# PlacaAquisicao.net
KiCad netlist of a schematic drawn in EAGLE
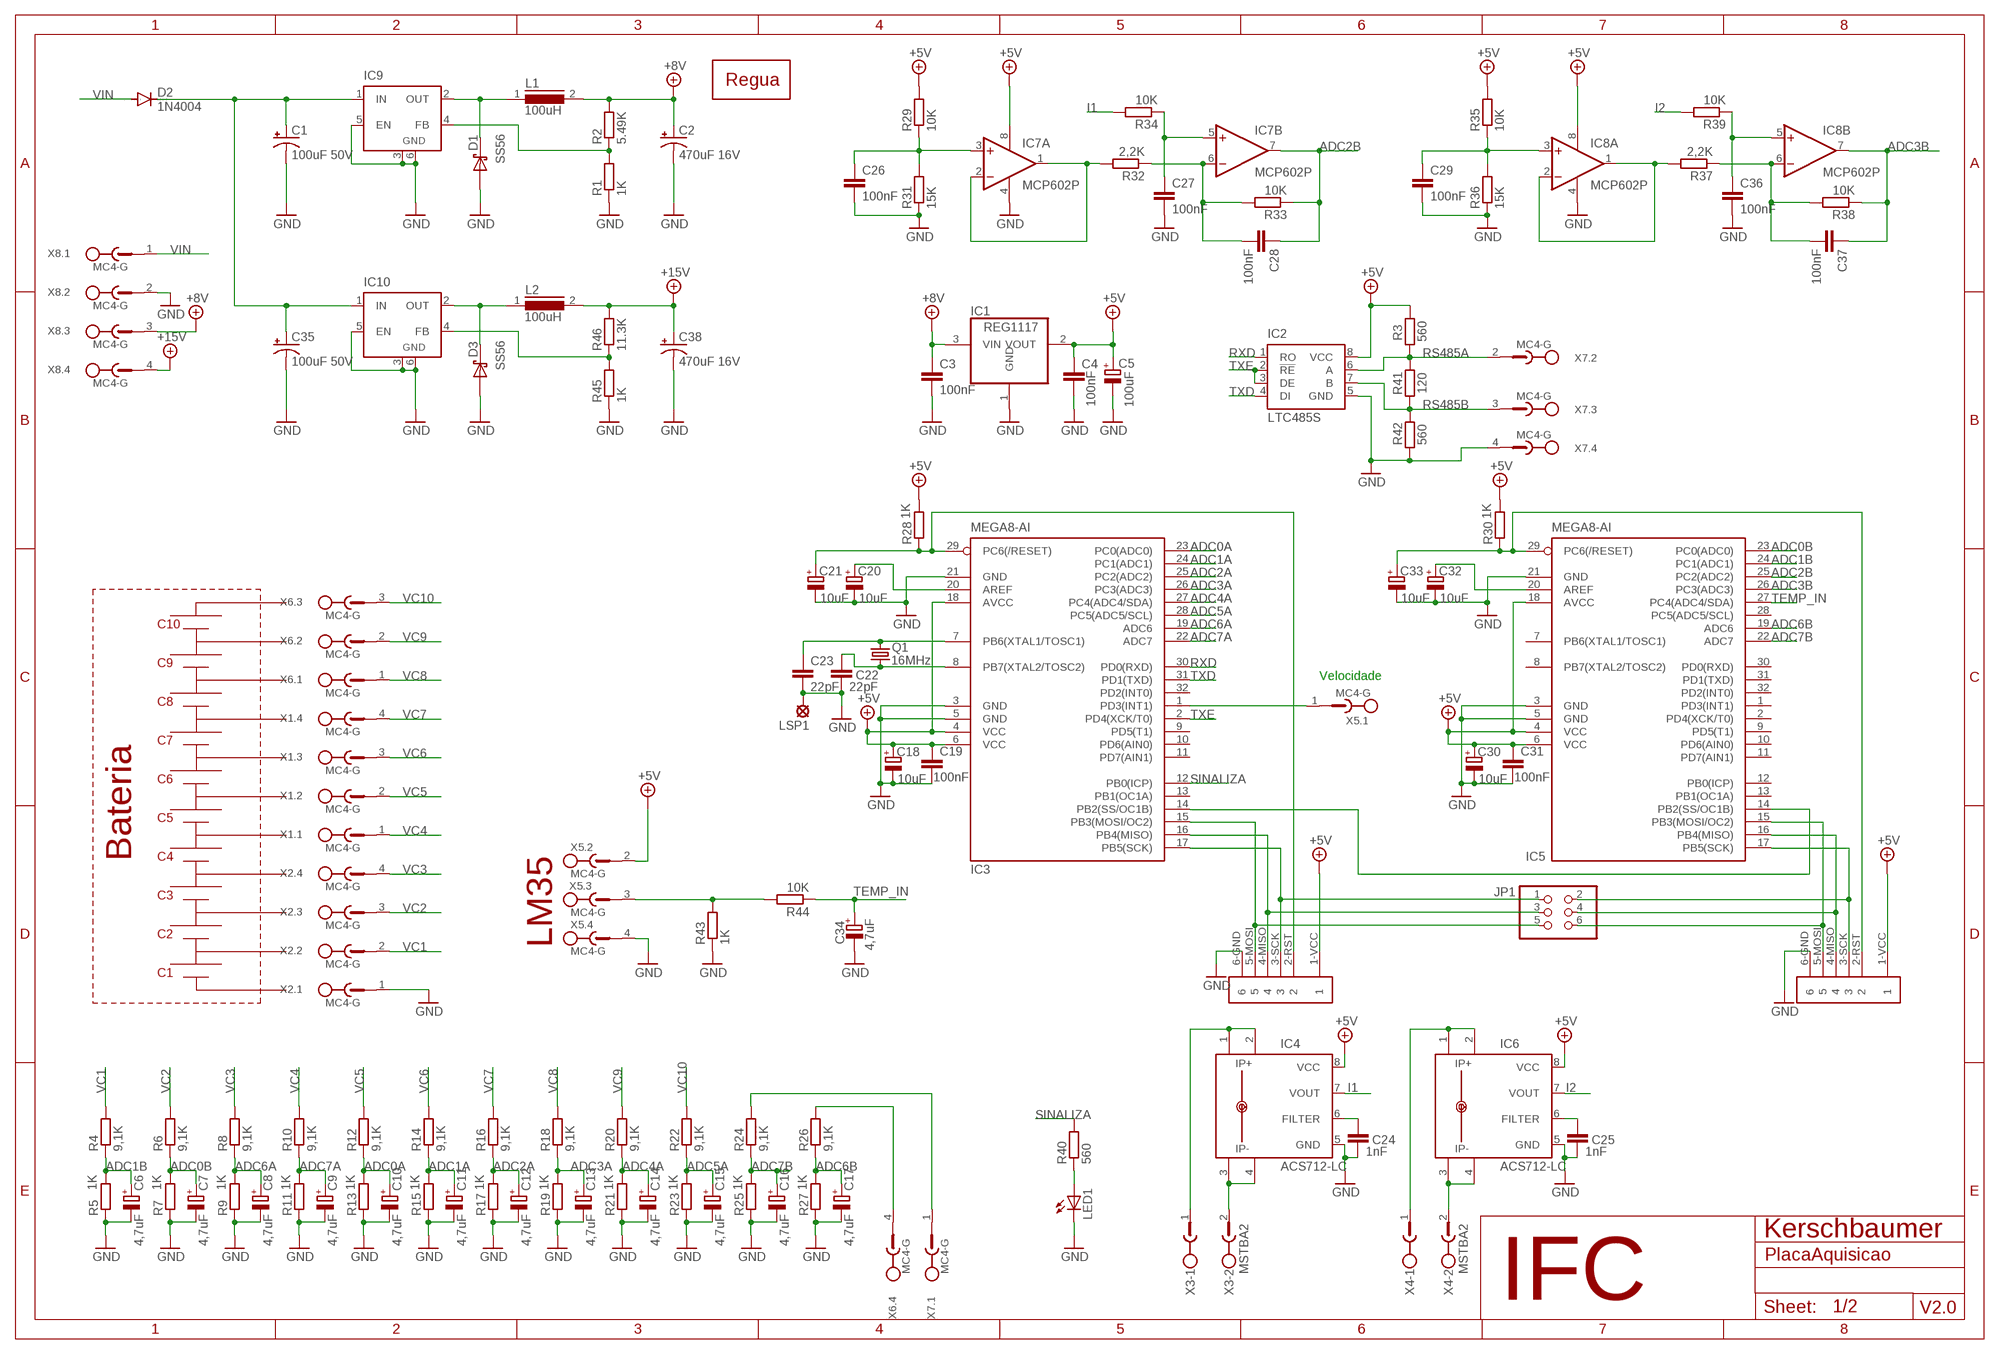
[diagram p0: schematic, sheet 1]
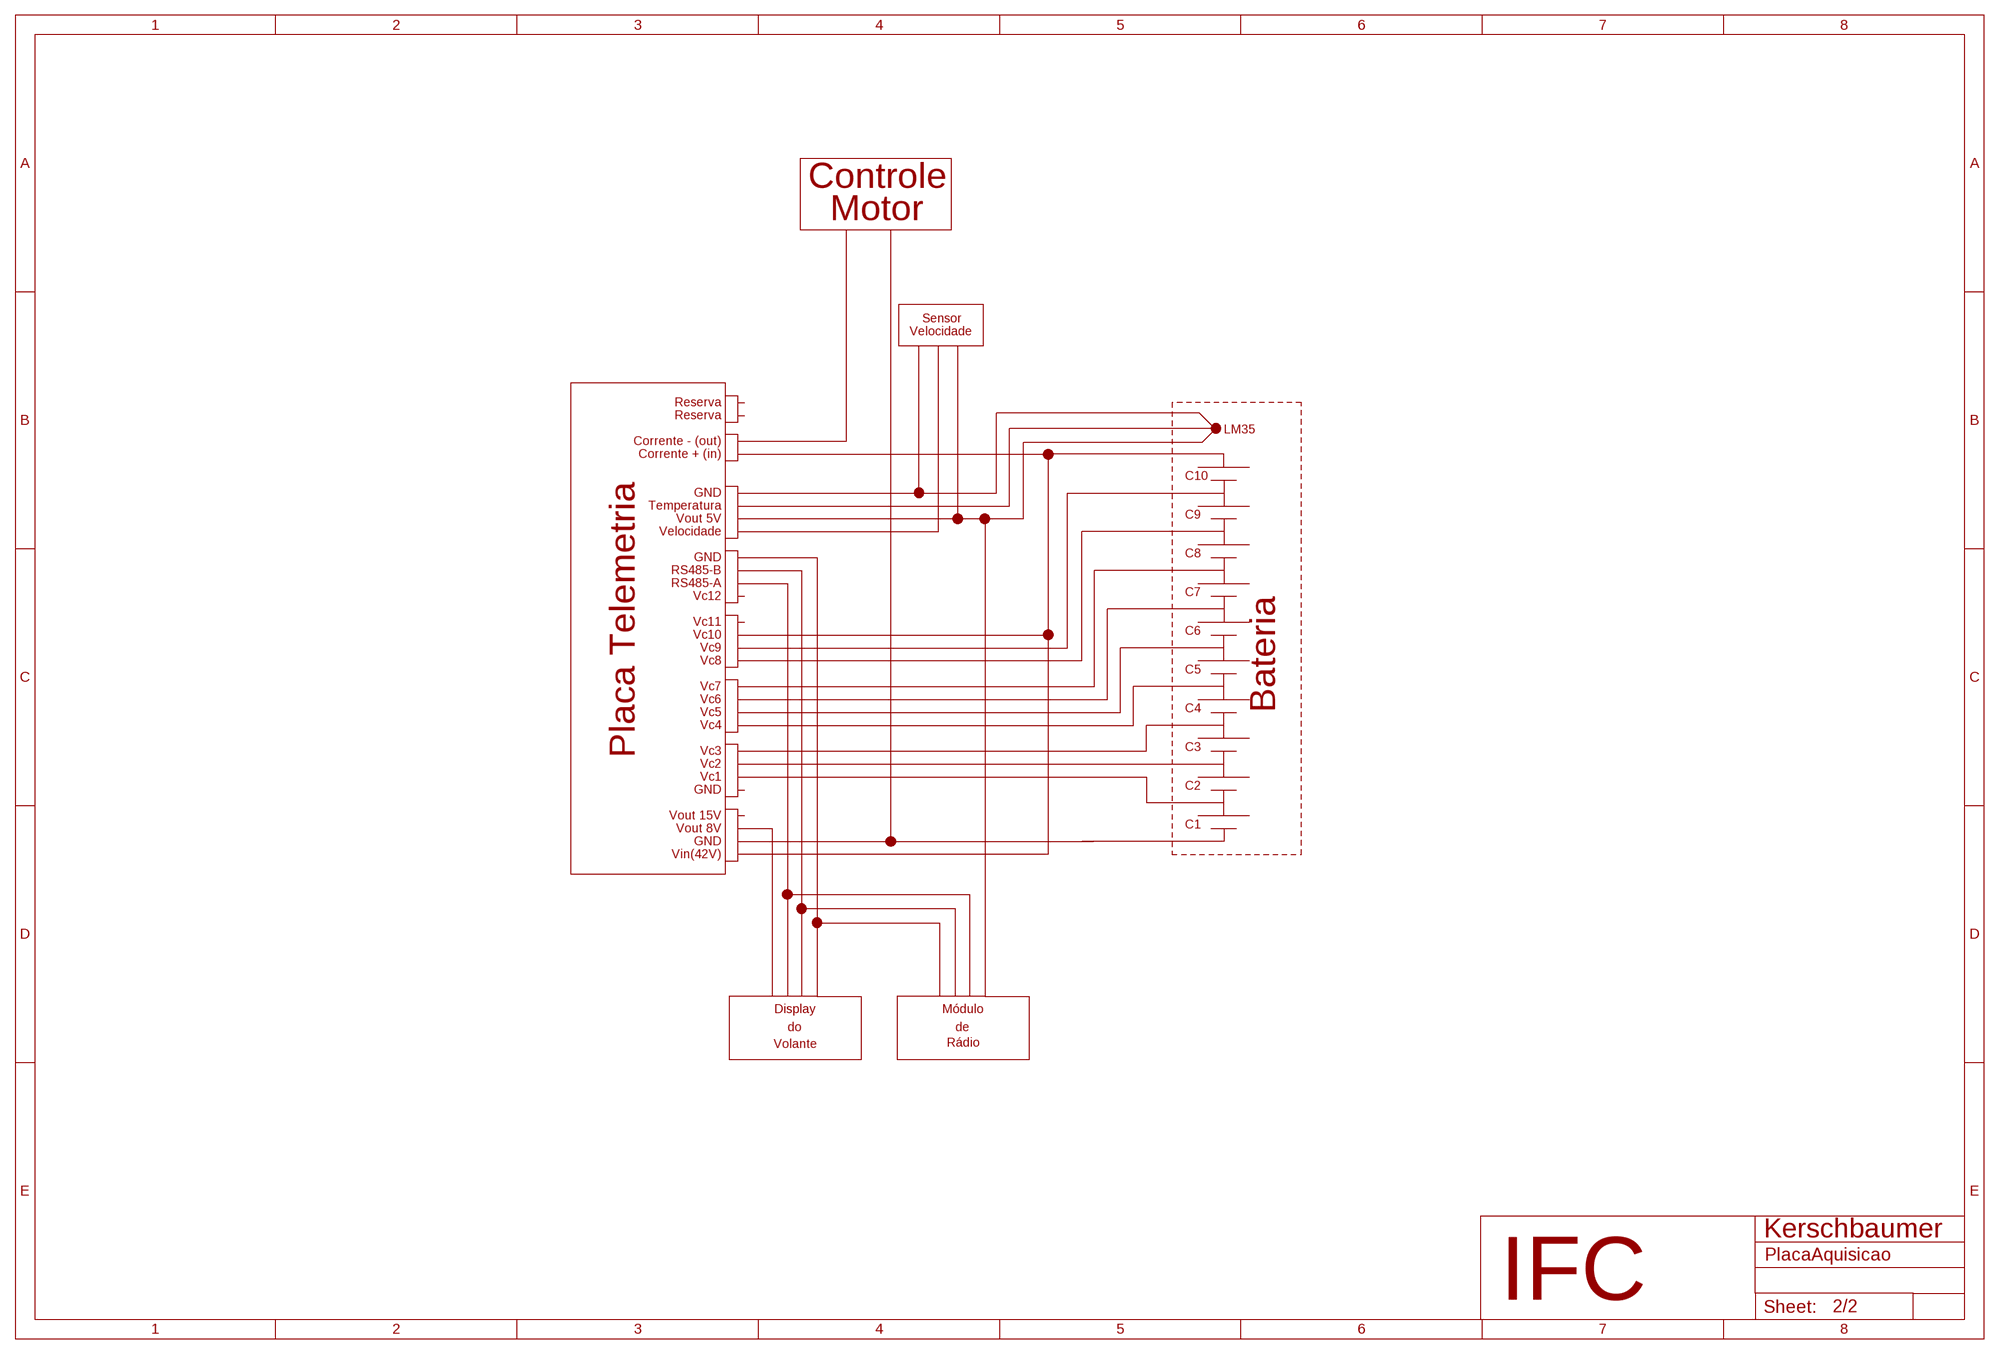
[diagram p1: schematic, sheet 2]

(export (version "E")
  (design (tool "Eeschema 10.0.6"))
  (components
    (comp (ref "C1")
      (value "100uF 50V")
      (footprint "eagle-import:E2,5-7")
      (libsource (lib "eagle-import") (part "CPOL-USE2.5-7"))
    )
    (comp (ref "C2")
      (value "470uF 16V")
      (footprint "eagle-import:E2,5-7")
      (libsource (lib "eagle-import") (part "CPOL-USE2.5-7"))
    )
    (comp (ref "C3")
      (value "100nF")
      (footprint "eagle-import:C050-025X075")
      (libsource (lib "eagle-import") (part "C-EU050-025X075"))
    )
    (comp (ref "C4")
      (value "100nF")
      (footprint "eagle-import:C050-025X075")
      (libsource (lib "eagle-import") (part "C-EU050-025X075"))
    )
    (comp (ref "C5")
      (value "100uF")
      (footprint "eagle-import:E2,5-6")
      (libsource (lib "eagle-import") (part "CPOL-EUE2.5-6"))
    )
    (comp (ref "C6")
      (value "4,7uF")
      (footprint "eagle-import:E2,5-6")
      (libsource (lib "eagle-import") (part "CPOL-EUE2.5-6"))
    )
    (comp (ref "C7")
      (value "4,7uF")
      (footprint "eagle-import:E2,5-6")
      (libsource (lib "eagle-import") (part "CPOL-EUE2.5-6"))
    )
    (comp (ref "C8")
      (value "4,7uF")
      (footprint "eagle-import:E2,5-6")
      (libsource (lib "eagle-import") (part "CPOL-EUE2.5-6"))
    )
    (comp (ref "C9")
      (value "4,7uF")
      (footprint "eagle-import:E2,5-6")
      (libsource (lib "eagle-import") (part "CPOL-EUE2.5-6"))
    )
    (comp (ref "C10")
      (value "4,7uF")
      (footprint "eagle-import:E2,5-6")
      (libsource (lib "eagle-import") (part "CPOL-EUE2.5-6"))
    )
    (comp (ref "C11")
      (value "4,7uF")
      (footprint "eagle-import:E2,5-6")
      (libsource (lib "eagle-import") (part "CPOL-EUE2.5-6"))
    )
    (comp (ref "C12")
      (value "4,7uF")
      (footprint "eagle-import:E2,5-6")
      (libsource (lib "eagle-import") (part "CPOL-EUE2.5-6"))
    )
    (comp (ref "C13")
      (value "4,7uF")
      (footprint "eagle-import:E2,5-6")
      (libsource (lib "eagle-import") (part "CPOL-EUE2.5-6"))
    )
    (comp (ref "C14")
      (value "4,7uF")
      (footprint "eagle-import:E2,5-6")
      (libsource (lib "eagle-import") (part "CPOL-EUE2.5-6"))
    )
    (comp (ref "C15")
      (value "4,7uF")
      (footprint "eagle-import:E2,5-6")
      (libsource (lib "eagle-import") (part "CPOL-EUE2.5-6"))
    )
    (comp (ref "C16")
      (value "4,7uF")
      (footprint "eagle-import:E2,5-6")
      (libsource (lib "eagle-import") (part "CPOL-EUE2.5-6"))
    )
    (comp (ref "C17")
      (value "4,7uF")
      (footprint "eagle-import:E2,5-6")
      (libsource (lib "eagle-import") (part "CPOL-EUE2.5-6"))
    )
    (comp (ref "C18")
      (value "10uF")
      (footprint "eagle-import:E2,5-6")
      (libsource (lib "eagle-import") (part "CPOL-EUE2.5-6"))
    )
    (comp (ref "C19")
      (value "100nF")
      (footprint "eagle-import:C050-025X075")
      (libsource (lib "eagle-import") (part "C-EU050-025X075"))
    )
    (comp (ref "C20")
      (value "10uF")
      (footprint "eagle-import:E2,5-6")
      (libsource (lib "eagle-import") (part "CPOL-EUE2.5-6"))
    )
    (comp (ref "C21")
      (value "10uF")
      (footprint "eagle-import:E2,5-6")
      (libsource (lib "eagle-import") (part "CPOL-EUE2.5-6"))
    )
    (comp (ref "C22")
      (value "22pF")
      (footprint "eagle-import:C025-025X050")
      (libsource (lib "eagle-import") (part "C-EU025-025X050"))
    )
    (comp (ref "C23")
      (value "22pF")
      (footprint "eagle-import:C025-025X050")
      (libsource (lib "eagle-import") (part "C-EU025-025X050"))
    )
    (comp (ref "C24")
      (value "1nF")
      (footprint "eagle-import:C025-025X050")
      (libsource (lib "eagle-import") (part "C-EU025-025X050"))
    )
    (comp (ref "C25")
      (value "1nF")
      (footprint "eagle-import:C025-025X050")
      (libsource (lib "eagle-import") (part "C-EU025-025X050"))
    )
    (comp (ref "C26")
      (value "100nF")
      (footprint "eagle-import:C050-025X075")
      (libsource (lib "eagle-import") (part "C-EU050-025X075"))
    )
    (comp (ref "C27")
      (value "100nF")
      (footprint "eagle-import:C050-025X075")
      (libsource (lib "eagle-import") (part "C-EU050-025X075"))
    )
    (comp (ref "C28")
      (value "100nF")
      (footprint "eagle-import:C050-025X075")
      (libsource (lib "eagle-import") (part "C-EU050-025X075"))
    )
    (comp (ref "C29")
      (value "100nF")
      (footprint "eagle-import:C050-025X075")
      (libsource (lib "eagle-import") (part "C-EU050-025X075"))
    )
    (comp (ref "C30")
      (value "10uF")
      (footprint "eagle-import:E2,5-6")
      (libsource (lib "eagle-import") (part "CPOL-EUE2.5-6"))
    )
    (comp (ref "C31")
      (value "100nF")
      (footprint "eagle-import:C050-025X075")
      (libsource (lib "eagle-import") (part "C-EU050-025X075"))
    )
    (comp (ref "C32")
      (value "10uF")
      (footprint "eagle-import:E2,5-6")
      (libsource (lib "eagle-import") (part "CPOL-EUE2.5-6"))
    )
    (comp (ref "C33")
      (value "10uF")
      (footprint "eagle-import:E2,5-6")
      (libsource (lib "eagle-import") (part "CPOL-EUE2.5-6"))
    )
    (comp (ref "C34")
      (value "4,7uF")
      (footprint "eagle-import:E2,5-6")
      (libsource (lib "eagle-import") (part "CPOL-EUE2.5-6"))
    )
    (comp (ref "C35")
      (value "100uF 50V")
      (footprint "eagle-import:E2,5-7")
      (libsource (lib "eagle-import") (part "CPOL-USE2.5-7"))
    )
    (comp (ref "C36")
      (value "100nF")
      (footprint "eagle-import:C050-025X075")
      (libsource (lib "eagle-import") (part "C-EU050-025X075"))
    )
    (comp (ref "C37")
      (value "100nF")
      (footprint "eagle-import:C050-025X075")
      (libsource (lib "eagle-import") (part "C-EU050-025X075"))
    )
    (comp (ref "C38")
      (value "470uF 16V")
      (footprint "eagle-import:E2,5-7")
      (libsource (lib "eagle-import") (part "CPOL-USE2.5-7"))
    )
    (comp (ref "D1")
      (value "SS56")
      (footprint "eagle-import:SMA-DIODE")
      (libsource (lib "eagle-import") (part "DIODE-SCHOTTKY_"))
    )
    (comp (ref "D2")
      (value "1N4004")
      (footprint "eagle-import:DO41-10")
      (libsource (lib "eagle-import") (part "1N4004"))
    )
    (comp (ref "D3")
      (value "SS56")
      (footprint "eagle-import:SMA-DIODE")
      (libsource (lib "eagle-import") (part "DIODE-SCHOTTKY_"))
    )
    (comp (ref "IC1")
      (value "REG1117")
      (footprint "eagle-import:SOT223")
      (libsource (lib "eagle-import") (part "REG1117"))
    )
    (comp (ref "IC2")
      (value "LTC485S")
      (footprint "eagle-import:SOIC8")
      (libsource (lib "eagle-import") (part "LTC485S"))
    )
    (comp (ref "IC3")
      (value "MEGA8-AI")
      (footprint "eagle-import:TQFP32-08")
      (fields (field (name "MPN") "ATMEGA8-16AU"))
      (libsource (lib "eagle-import") (part "MEGA8-AI"))
    )
    (comp (ref "IC4")
      (value "ACS712-LC")
      (footprint "eagle-import:SOIC8")
      (libsource (lib "eagle-import") (part "ACS712-LC"))
    )
    (comp (ref "IC5")
      (value "MEGA8-AI")
      (footprint "eagle-import:TQFP32-08")
      (fields (field (name "MPN") "ATMEGA8-16AU"))
      (libsource (lib "eagle-import") (part "MEGA8-AI"))
    )
    (comp (ref "IC6")
      (value "ACS712-LC")
      (footprint "eagle-import:SOIC8")
      (libsource (lib "eagle-import") (part "ACS712-LC"))
    )
    (comp (ref "IC7")
      (value "MCP602P")
      (footprint "eagle-import:DIL08")
      (libsource (lib "eagle-import") (part "MCP602P"))
    )
    (comp (ref "IC8")
      (value "MCP602P")
      (footprint "eagle-import:DIL08")
      (libsource (lib "eagle-import") (part "MCP602P"))
    )
    (comp (ref "IC9")
      (value "LM2596S")
      (footprint "eagle-import:TO263-5")
      (libsource (lib "eagle-import") (part "LM2596S"))
    )
    (comp (ref "IC10")
      (value "LM2596S")
      (footprint "eagle-import:TO263-5")
      (libsource (lib "eagle-import") (part "LM2596S"))
    )
    (comp (ref "JP1")
      (value "PINHD-2X3")
      (footprint "eagle-import:2X03")
      (libsource (lib "eagle-import") (part "PINHD-2X3"))
    )
    (comp (ref "L1")
      (value "100uH")
      (footprint "eagle-import:DR125")
      (libsource (lib "eagle-import") (part "DR125"))
    )
    (comp (ref "L2")
      (value "100uH")
      (footprint "eagle-import:DR125")
      (libsource (lib "eagle-import") (part "DR125"))
    )
    (comp (ref "LED1")
      (value "LED3MM")
      (footprint "eagle-import:LED3MM")
      (libsource (lib "eagle-import") (part "LED3MM"))
    )
    (comp (ref "LSP1")
      (value "LSP10")
      (footprint "eagle-import:LSP10")
      (libsource (lib "eagle-import") (part "LSP10"))
    )
    (comp (ref "P1")
      (value "SPI")
      (footprint "eagle-import:SPI")
      (libsource (lib "eagle-import") (part "SPI"))
    )
    (comp (ref "P2")
      (value "SPI")
      (footprint "eagle-import:SPI")
      (libsource (lib "eagle-import") (part "SPI"))
    )
    (comp (ref "Q1")
      (value "16MHz")
      (footprint "eagle-import:HC49_S")
      (libsource (lib "eagle-import") (part "CRYSTALHC49S"))
    )
    (comp (ref "R1")
      (value "1K")
      (footprint "eagle-import:0207_7")
      (libsource (lib "eagle-import") (part "R-EU_0207/7"))
    )
    (comp (ref "R2")
      (value "5.49K")
      (footprint "eagle-import:0207_7")
      (libsource (lib "eagle-import") (part "R-EU_0207/7"))
    )
    (comp (ref "R3")
      (value "560")
      (footprint "eagle-import:0207_7")
      (libsource (lib "eagle-import") (part "R-EU_0207/7"))
    )
    (comp (ref "R4")
      (value "9,1K")
      (footprint "eagle-import:0207_7")
      (libsource (lib "eagle-import") (part "R-EU_0207/7"))
    )
    (comp (ref "R5")
      (value "1K")
      (footprint "eagle-import:0207_7")
      (libsource (lib "eagle-import") (part "R-EU_0207/7"))
    )
    (comp (ref "R6")
      (value "9,1K")
      (footprint "eagle-import:0207_7")
      (libsource (lib "eagle-import") (part "R-EU_0207/7"))
    )
    (comp (ref "R7")
      (value "1K")
      (footprint "eagle-import:0207_7")
      (libsource (lib "eagle-import") (part "R-EU_0207/7"))
    )
    (comp (ref "R8")
      (value "9,1K")
      (footprint "eagle-import:0207_7")
      (libsource (lib "eagle-import") (part "R-EU_0207/7"))
    )
    (comp (ref "R9")
      (value "1K")
      (footprint "eagle-import:0207_7")
      (libsource (lib "eagle-import") (part "R-EU_0207/7"))
    )
    (comp (ref "R10")
      (value "9,1K")
      (footprint "eagle-import:0207_7")
      (libsource (lib "eagle-import") (part "R-EU_0207/7"))
    )
    (comp (ref "R11")
      (value "1K")
      (footprint "eagle-import:0207_7")
      (libsource (lib "eagle-import") (part "R-EU_0207/7"))
    )
    (comp (ref "R12")
      (value "9,1K")
      (footprint "eagle-import:0207_7")
      (libsource (lib "eagle-import") (part "R-EU_0207/7"))
    )
    (comp (ref "R13")
      (value "1K")
      (footprint "eagle-import:0207_7")
      (libsource (lib "eagle-import") (part "R-EU_0207/7"))
    )
    (comp (ref "R14")
      (value "9,1K")
      (footprint "eagle-import:0207_7")
      (libsource (lib "eagle-import") (part "R-EU_0207/7"))
    )
    (comp (ref "R15")
      (value "1K")
      (footprint "eagle-import:0207_7")
      (libsource (lib "eagle-import") (part "R-EU_0207/7"))
    )
    (comp (ref "R16")
      (value "9,1K")
      (footprint "eagle-import:0207_7")
      (libsource (lib "eagle-import") (part "R-EU_0207/7"))
    )
    (comp (ref "R17")
      (value "1K")
      (footprint "eagle-import:0207_7")
      (libsource (lib "eagle-import") (part "R-EU_0207/7"))
    )
    (comp (ref "R18")
      (value "9,1K")
      (footprint "eagle-import:0207_7")
      (libsource (lib "eagle-import") (part "R-EU_0207/7"))
    )
    (comp (ref "R19")
      (value "1K")
      (footprint "eagle-import:0207_7")
      (libsource (lib "eagle-import") (part "R-EU_0207/7"))
    )
    (comp (ref "R20")
      (value "9,1K")
      (footprint "eagle-import:0207_7")
      (libsource (lib "eagle-import") (part "R-EU_0207/7"))
    )
    (comp (ref "R21")
      (value "1K")
      (footprint "eagle-import:0207_7")
      (libsource (lib "eagle-import") (part "R-EU_0207/7"))
    )
    (comp (ref "R22")
      (value "9,1K")
      (footprint "eagle-import:0207_7")
      (libsource (lib "eagle-import") (part "R-EU_0207/7"))
    )
    (comp (ref "R23")
      (value "1K")
      (footprint "eagle-import:0207_7")
      (libsource (lib "eagle-import") (part "R-EU_0207/7"))
    )
    (comp (ref "R24")
      (value "9,1K")
      (footprint "eagle-import:0207_7")
      (libsource (lib "eagle-import") (part "R-EU_0207/7"))
    )
    (comp (ref "R25")
      (value "1K")
      (footprint "eagle-import:0207_7")
      (libsource (lib "eagle-import") (part "R-EU_0207/7"))
    )
    (comp (ref "R26")
      (value "9,1K")
      (footprint "eagle-import:0207_7")
      (libsource (lib "eagle-import") (part "R-EU_0207/7"))
    )
    (comp (ref "R27")
      (value "1K")
      (footprint "eagle-import:0207_7")
      (libsource (lib "eagle-import") (part "R-EU_0207/7"))
    )
    (comp (ref "R28")
      (value "1K")
      (footprint "eagle-import:0207_7")
      (libsource (lib "eagle-import") (part "R-EU_0207/7"))
    )
    (comp (ref "R29")
      (value "10K")
      (footprint "eagle-import:0207_7")
      (libsource (lib "eagle-import") (part "R-EU_0207/7"))
    )
    (comp (ref "R30")
      (value "1K")
      (footprint "eagle-import:0207_7")
      (libsource (lib "eagle-import") (part "R-EU_0207/7"))
    )
    (comp (ref "R31")
      (value "15K")
      (footprint "eagle-import:0207_7")
      (libsource (lib "eagle-import") (part "R-EU_0207/7"))
    )
    (comp (ref "R32")
      (value "2,2K")
      (footprint "eagle-import:0207_7")
      (libsource (lib "eagle-import") (part "R-EU_0207/7"))
    )
    (comp (ref "R33")
      (value "10K")
      (footprint "eagle-import:0207_7")
      (libsource (lib "eagle-import") (part "R-EU_0207/7"))
    )
    (comp (ref "R34")
      (value "10K")
      (footprint "eagle-import:0207_7")
      (libsource (lib "eagle-import") (part "R-EU_0207/7"))
    )
    (comp (ref "R35")
      (value "10K")
      (footprint "eagle-import:0207_7")
      (libsource (lib "eagle-import") (part "R-EU_0207/7"))
    )
    (comp (ref "R36")
      (value "15K")
      (footprint "eagle-import:0207_7")
      (libsource (lib "eagle-import") (part "R-EU_0207/7"))
    )
    (comp (ref "R37")
      (value "2,2K")
      (footprint "eagle-import:0207_7")
      (libsource (lib "eagle-import") (part "R-EU_0207/7"))
    )
    (comp (ref "R38")
      (value "10K")
      (footprint "eagle-import:0207_7")
      (libsource (lib "eagle-import") (part "R-EU_0207/7"))
    )
    (comp (ref "R39")
      (value "10K")
      (footprint "eagle-import:0207_7")
      (libsource (lib "eagle-import") (part "R-EU_0207/7"))
    )
    (comp (ref "R40")
      (value "560")
      (footprint "eagle-import:0207_7")
      (libsource (lib "eagle-import") (part "R-EU_0207/7"))
    )
    (comp (ref "R41")
      (value "120")
      (footprint "eagle-import:0207_7")
      (libsource (lib "eagle-import") (part "R-EU_0207/7"))
    )
    (comp (ref "R42")
      (value "560")
      (footprint "eagle-import:0207_7")
      (libsource (lib "eagle-import") (part "R-EU_0207/7"))
    )
    (comp (ref "R43")
      (value "1K")
      (footprint "eagle-import:0207_7")
      (libsource (lib "eagle-import") (part "R-EU_0207/7"))
    )
    (comp (ref "R44")
      (value "10K")
      (footprint "eagle-import:0207_7")
      (libsource (lib "eagle-import") (part "R-EU_0207/7"))
    )
    (comp (ref "R45")
      (value "1K")
      (footprint "eagle-import:0207_7")
      (libsource (lib "eagle-import") (part "R-EU_0207/7"))
    )
    (comp (ref "R46")
      (value "11.3K")
      (footprint "eagle-import:0207_7")
      (libsource (lib "eagle-import") (part "R-EU_0207/7"))
    )
    (comp (ref "U$1")
      (value "REGUA")
      (footprint "eagle-import:REGUA")
      (libsource (lib "eagle-import") (part "REGUA"))
    )
    (comp (ref "X1")
      (value "MC4-G")
      (footprint "eagle-import:MC4-G")
      (libsource (lib "eagle-import") (part "MC4-G"))
    )
    (comp (ref "X2")
      (value "MC4-G")
      (footprint "eagle-import:MC4-G")
      (libsource (lib "eagle-import") (part "MC4-G"))
    )
    (comp (ref "X3")
      (value "MSTBA2")
      (footprint "eagle-import:MSTBA2")
      (fields (field (name "MF") "FARNELL") (field (name "MPN") "1757242"))
      (libsource (lib "eagle-import") (part "MSTBA2"))
    )
    (comp (ref "X4")
      (value "MSTBA2")
      (footprint "eagle-import:MSTBA2")
      (fields (field (name "MF") "FARNELL") (field (name "MPN") "1757242"))
      (libsource (lib "eagle-import") (part "MSTBA2"))
    )
    (comp (ref "X5")
      (value "MC4-G")
      (footprint "eagle-import:MC4-G")
      (libsource (lib "eagle-import") (part "MC4-G"))
    )
    (comp (ref "X6")
      (value "MC4-G")
      (footprint "eagle-import:MC4-G")
      (libsource (lib "eagle-import") (part "MC4-G"))
    )
    (comp (ref "X7")
      (value "MC4-G")
      (footprint "eagle-import:MC4-G")
      (libsource (lib "eagle-import") (part "MC4-G"))
    )
    (comp (ref "X8")
      (value "MC4-G")
      (footprint "eagle-import:MC4-G")
      (libsource (lib "eagle-import") (part "MC4-G"))
    )
  )
  (nets
    (net (code "1") (name "+5V") (class "Default")
      (node (ref "C18") (pin "+") (pinfunction "+_+") (pintype "passive"))
      (node (ref "C19") (pin "1") (pinfunction "1_1") (pintype "passive"))
      (node (ref "C30") (pin "+") (pinfunction "+_+") (pintype "passive"))
      (node (ref "C31") (pin "1") (pinfunction "1_1") (pintype "passive"))
      (node (ref "C4") (pin "1") (pinfunction "1_1") (pintype "passive"))
      (node (ref "C5") (pin "+") (pinfunction "+_+") (pintype "passive"))
      (node (ref "IC1") (pin "2") (pinfunction "VOUT_2") (pintype "output"))
      (node (ref "IC2") (pin "8") (pinfunction "VCC_8") (pintype "input"))
      (node (ref "IC3") (pin "18") (pinfunction "AVCC_18") (pintype "power_in"))
      (node (ref "IC3") (pin "4") (pinfunction "VCC_4") (pintype "power_in"))
      (node (ref "IC3") (pin "6") (pinfunction "VCC_6") (pintype "power_in"))
      (node (ref "IC4") (pin "8") (pinfunction "VCC_8") (pintype "power_in"))
      (node (ref "IC5") (pin "18") (pinfunction "AVCC_18") (pintype "power_in"))
      (node (ref "IC5") (pin "4") (pinfunction "VCC_4") (pintype "power_in"))
      (node (ref "IC5") (pin "6") (pinfunction "VCC_6") (pintype "power_in"))
      (node (ref "IC6") (pin "8") (pinfunction "VCC_8") (pintype "power_in"))
      (node (ref "IC7") (pin "8") (pinfunction "V+_8") (pintype "power_in"))
      (node (ref "IC8") (pin "8") (pinfunction "V+_8") (pintype "power_in"))
      (node (ref "P1") (pin "1-VCC") (pinfunction "1_1-VCC") (pintype "bidirectional"))
      (node (ref "P2") (pin "1-VCC") (pinfunction "1_1-VCC") (pintype "bidirectional"))
      (node (ref "R28") (pin "2") (pinfunction "2_2") (pintype "passive"))
      (node (ref "R29") (pin "2") (pinfunction "2_2") (pintype "passive"))
      (node (ref "R3") (pin "2") (pinfunction "2_2") (pintype "passive"))
      (node (ref "R30") (pin "2") (pinfunction "2_2") (pintype "passive"))
      (node (ref "R35") (pin "2") (pinfunction "2_2") (pintype "passive"))
      (node (ref "X5") (pin "2") (pinfunction "SK_2") (pintype "passive"))
    )
    (net (code "2") (name "+8V") (class "Default")
      (node (ref "C2") (pin "+") (pinfunction "+_+") (pintype "passive"))
      (node (ref "C3") (pin "1") (pinfunction "1_1") (pintype "passive"))
      (node (ref "IC1") (pin "3") (pinfunction "VIN_3") (pintype "input"))
      (node (ref "L1") (pin "2") (pinfunction "2_2") (pintype "passive"))
      (node (ref "R2") (pin "2") (pinfunction "2_2") (pintype "passive"))
      (node (ref "X8") (pin "3") (pinfunction "SK_3") (pintype "passive"))
    )
    (net (code "3") (name "+15V") (class "Default")
      (node (ref "C38") (pin "+") (pinfunction "+_+") (pintype "passive"))
      (node (ref "L2") (pin "2") (pinfunction "2_2") (pintype "passive"))
      (node (ref "R46") (pin "2") (pinfunction "2_2") (pintype "passive"))
      (node (ref "X8") (pin "4") (pinfunction "SK_4") (pintype "passive"))
    )
    (net (code "4") (name "ADC0A") (class "Default")
      (node (ref "C10") (pin "+") (pinfunction "+_+") (pintype "passive"))
      (node (ref "IC3") (pin "23") (pinfunction "PC0(ADC0)_23") (pintype "bidirectional"))
      (node (ref "R12") (pin "1") (pinfunction "1_1") (pintype "passive"))
      (node (ref "R13") (pin "2") (pinfunction "2_2") (pintype "passive"))
    )
    (net (code "5") (name "ADC0B") (class "Default")
      (node (ref "C7") (pin "+") (pinfunction "+_+") (pintype "passive"))
      (node (ref "IC5") (pin "23") (pinfunction "PC0(ADC0)_23") (pintype "bidirectional"))
      (node (ref "R6") (pin "1") (pinfunction "1_1") (pintype "passive"))
      (node (ref "R7") (pin "2") (pinfunction "2_2") (pintype "passive"))
    )
    (net (code "6") (name "ADC1A") (class "Default")
      (node (ref "C11") (pin "+") (pinfunction "+_+") (pintype "passive"))
      (node (ref "IC3") (pin "24") (pinfunction "PC1(ADC1)_24") (pintype "bidirectional"))
      (node (ref "R14") (pin "1") (pinfunction "1_1") (pintype "passive"))
      (node (ref "R15") (pin "2") (pinfunction "2_2") (pintype "passive"))
    )
    (net (code "7") (name "ADC1B") (class "Default")
      (node (ref "C6") (pin "+") (pinfunction "+_+") (pintype "passive"))
      (node (ref "IC5") (pin "24") (pinfunction "PC1(ADC1)_24") (pintype "bidirectional"))
      (node (ref "R4") (pin "1") (pinfunction "1_1") (pintype "passive"))
      (node (ref "R5") (pin "2") (pinfunction "2_2") (pintype "passive"))
    )
    (net (code "8") (name "ADC2A") (class "Default")
      (node (ref "C12") (pin "+") (pinfunction "+_+") (pintype "passive"))
      (node (ref "IC3") (pin "25") (pinfunction "PC2(ADC2)_25") (pintype "bidirectional"))
      (node (ref "R16") (pin "1") (pinfunction "1_1") (pintype "passive"))
      (node (ref "R17") (pin "2") (pinfunction "2_2") (pintype "passive"))
    )
    (net (code "9") (name "ADC2B") (class "Default")
      (node (ref "C28") (pin "1") (pinfunction "1_1") (pintype "passive"))
      (node (ref "IC5") (pin "25") (pinfunction "PC2(ADC2)_25") (pintype "bidirectional"))
      (node (ref "IC7") (pin "7") (pinfunction "OUT_7") (pintype "output"))
      (node (ref "R33") (pin "1") (pinfunction "1_1") (pintype "passive"))
    )
    (net (code "10") (name "ADC3A") (class "Default")
      (node (ref "C13") (pin "+") (pinfunction "+_+") (pintype "passive"))
      (node (ref "IC3") (pin "26") (pinfunction "PC3(ADC3)_26") (pintype "bidirectional"))
      (node (ref "R18") (pin "1") (pinfunction "1_1") (pintype "passive"))
      (node (ref "R19") (pin "2") (pinfunction "2_2") (pintype "passive"))
    )
    (net (code "11") (name "ADC3B") (class "Default")
      (node (ref "C37") (pin "1") (pinfunction "1_1") (pintype "passive"))
      (node (ref "IC5") (pin "26") (pinfunction "PC3(ADC3)_26") (pintype "bidirectional"))
      (node (ref "IC8") (pin "7") (pinfunction "OUT_7") (pintype "output"))
      (node (ref "R38") (pin "1") (pinfunction "1_1") (pintype "passive"))
    )
    (net (code "12") (name "ADC4A") (class "Default")
      (node (ref "C14") (pin "+") (pinfunction "+_+") (pintype "passive"))
      (node (ref "IC3") (pin "27") (pinfunction "PC4(ADC4/SDA)_27") (pintype "bidirectional"))
      (node (ref "R20") (pin "1") (pinfunction "1_1") (pintype "passive"))
      (node (ref "R21") (pin "2") (pinfunction "2_2") (pintype "passive"))
    )
    (net (code "13") (name "ADC5A") (class "Default")
      (node (ref "C15") (pin "+") (pinfunction "+_+") (pintype "passive"))
      (node (ref "IC3") (pin "28") (pinfunction "PC5(ADC5/SCL)_28") (pintype "bidirectional"))
      (node (ref "R22") (pin "1") (pinfunction "1_1") (pintype "passive"))
      (node (ref "R23") (pin "2") (pinfunction "2_2") (pintype "passive"))
    )
    (net (code "14") (name "ADC6A") (class "Default")
      (node (ref "C8") (pin "+") (pinfunction "+_+") (pintype "passive"))
      (node (ref "IC3") (pin "19") (pinfunction "ADC6_19") (pintype "bidirectional"))
      (node (ref "R8") (pin "1") (pinfunction "1_1") (pintype "passive"))
      (node (ref "R9") (pin "2") (pinfunction "2_2") (pintype "passive"))
    )
    (net (code "15") (name "ADC6B") (class "Default")
      (node (ref "C17") (pin "+") (pinfunction "+_+") (pintype "passive"))
      (node (ref "IC5") (pin "19") (pinfunction "ADC6_19") (pintype "bidirectional"))
      (node (ref "R26") (pin "1") (pinfunction "1_1") (pintype "passive"))
      (node (ref "R27") (pin "2") (pinfunction "2_2") (pintype "passive"))
    )
    (net (code "16") (name "ADC7A") (class "Default")
      (node (ref "C9") (pin "+") (pinfunction "+_+") (pintype "passive"))
      (node (ref "IC3") (pin "22") (pinfunction "ADC7_22") (pintype "bidirectional"))
      (node (ref "R10") (pin "1") (pinfunction "1_1") (pintype "passive"))
      (node (ref "R11") (pin "2") (pinfunction "2_2") (pintype "passive"))
    )
    (net (code "17") (name "ADC7B") (class "Default")
      (node (ref "C16") (pin "+") (pinfunction "+_+") (pintype "passive"))
      (node (ref "IC5") (pin "22") (pinfunction "ADC7_22") (pintype "bidirectional"))
      (node (ref "R24") (pin "1") (pinfunction "1_1") (pintype "passive"))
      (node (ref "R25") (pin "2") (pinfunction "2_2") (pintype "passive"))
    )
    (net (code "18") (name "GND") (class "Default")
      (node (ref "C1") (pin "-") (pinfunction "-_-") (pintype "passive"))
      (node (ref "C10") (pin "-") (pinfunction "-_-") (pintype "passive"))
      (node (ref "C11") (pin "-") (pinfunction "-_-") (pintype "passive"))
      (node (ref "C12") (pin "-") (pinfunction "-_-") (pintype "passive"))
      (node (ref "C13") (pin "-") (pinfunction "-_-") (pintype "passive"))
      (node (ref "C14") (pin "-") (pinfunction "-_-") (pintype "passive"))
      (node (ref "C15") (pin "-") (pinfunction "-_-") (pintype "passive"))
      (node (ref "C16") (pin "-") (pinfunction "-_-") (pintype "passive"))
      (node (ref "C17") (pin "-") (pinfunction "-_-") (pintype "passive"))
      (node (ref "C18") (pin "-") (pinfunction "-_-") (pintype "passive"))
      (node (ref "C19") (pin "2") (pinfunction "2_2") (pintype "passive"))
      (node (ref "C2") (pin "-") (pinfunction "-_-") (pintype "passive"))
      (node (ref "C20") (pin "-") (pinfunction "-_-") (pintype "passive"))
      (node (ref "C21") (pin "-") (pinfunction "-_-") (pintype "passive"))
      (node (ref "C22") (pin "2") (pinfunction "2_2") (pintype "passive"))
      (node (ref "C23") (pin "2") (pinfunction "2_2") (pintype "passive"))
      (node (ref "C24") (pin "2") (pinfunction "2_2") (pintype "passive"))
      (node (ref "C25") (pin "2") (pinfunction "2_2") (pintype "passive"))
      (node (ref "C26") (pin "2") (pinfunction "2_2") (pintype "passive"))
      (node (ref "C27") (pin "2") (pinfunction "2_2") (pintype "passive"))
      (node (ref "C29") (pin "2") (pinfunction "2_2") (pintype "passive"))
      (node (ref "C3") (pin "2") (pinfunction "2_2") (pintype "passive"))
      (node (ref "C30") (pin "-") (pinfunction "-_-") (pintype "passive"))
      (node (ref "C31") (pin "2") (pinfunction "2_2") (pintype "passive"))
      (node (ref "C32") (pin "-") (pinfunction "-_-") (pintype "passive"))
      (node (ref "C33") (pin "-") (pinfunction "-_-") (pintype "passive"))
      (node (ref "C34") (pin "-") (pinfunction "-_-") (pintype "passive"))
      (node (ref "C35") (pin "-") (pinfunction "-_-") (pintype "passive"))
      (node (ref "C36") (pin "2") (pinfunction "2_2") (pintype "passive"))
      (node (ref "C38") (pin "-") (pinfunction "-_-") (pintype "passive"))
      (node (ref "C4") (pin "2") (pinfunction "2_2") (pintype "passive"))
      (node (ref "C5") (pin "-") (pinfunction "-_-") (pintype "passive"))
      (node (ref "C6") (pin "-") (pinfunction "-_-") (pintype "passive"))
      (node (ref "C7") (pin "-") (pinfunction "-_-") (pintype "passive"))
      (node (ref "C8") (pin "-") (pinfunction "-_-") (pintype "passive"))
      (node (ref "C9") (pin "-") (pinfunction "-_-") (pintype "passive"))
      (node (ref "D1") (pin "A") (pinfunction "A_A") (pintype "passive"))
      (node (ref "D3") (pin "A") (pinfunction "A_A") (pintype "passive"))
      (node (ref "IC1") (pin "1") (pinfunction "GND_1") (pintype "power_in"))
      (node (ref "IC10") (pin "3") (pinfunction "GND_3") (pintype "power_in"))
      (node (ref "IC10") (pin "5") (pinfunction "EN_5") (pintype "input"))
      (node (ref "IC10") (pin "6") (pinfunction "GND_6") (pintype "power_in"))
      (node (ref "IC2") (pin "5") (pinfunction "GND_5") (pintype "input"))
      (node (ref "IC3") (pin "21") (pinfunction "GND_21") (pintype "power_in"))
      (node (ref "IC3") (pin "3") (pinfunction "GND_3") (pintype "power_in"))
      (node (ref "IC3") (pin "5") (pinfunction "GND_5") (pintype "power_in"))
      (node (ref "IC4") (pin "5") (pinfunction "GND_5") (pintype "power_in"))
      (node (ref "IC5") (pin "21") (pinfunction "GND_21") (pintype "power_in"))
      (node (ref "IC5") (pin "3") (pinfunction "GND_3") (pintype "power_in"))
      (node (ref "IC5") (pin "5") (pinfunction "GND_5") (pintype "power_in"))
      (node (ref "IC6") (pin "5") (pinfunction "GND_5") (pintype "power_in"))
      (node (ref "IC7") (pin "4") (pinfunction "V-_4") (pintype "power_in"))
      (node (ref "IC8") (pin "4") (pinfunction "V-_4") (pintype "power_in"))
      (node (ref "IC9") (pin "3") (pinfunction "GND_3") (pintype "power_in"))
      (node (ref "IC9") (pin "5") (pinfunction "EN_5") (pintype "input"))
      (node (ref "IC9") (pin "6") (pinfunction "GND_6") (pintype "power_in"))
      (node (ref "LED1") (pin "K") (pinfunction "C_K") (pintype "passive"))
      (node (ref "LSP1") (pin "MP") (pinfunction "MP_MP") (pintype "passive"))
      (node (ref "P1") (pin "6-GND") (pinfunction "6_6-GND") (pintype "bidirectional"))
      (node (ref "P2") (pin "6-GND") (pinfunction "6_6-GND") (pintype "bidirectional"))
      (node (ref "R1") (pin "1") (pinfunction "1_1") (pintype "passive"))
      (node (ref "R11") (pin "1") (pinfunction "1_1") (pintype "passive"))
      (node (ref "R13") (pin "1") (pinfunction "1_1") (pintype "passive"))
      (node (ref "R15") (pin "1") (pinfunction "1_1") (pintype "passive"))
      (node (ref "R17") (pin "1") (pinfunction "1_1") (pintype "passive"))
      (node (ref "R19") (pin "1") (pinfunction "1_1") (pintype "passive"))
      (node (ref "R21") (pin "1") (pinfunction "1_1") (pintype "passive"))
      (node (ref "R23") (pin "1") (pinfunction "1_1") (pintype "passive"))
      (node (ref "R25") (pin "1") (pinfunction "1_1") (pintype "passive"))
      (node (ref "R27") (pin "1") (pinfunction "1_1") (pintype "passive"))
      (node (ref "R31") (pin "1") (pinfunction "1_1") (pintype "passive"))
      (node (ref "R36") (pin "1") (pinfunction "1_1") (pintype "passive"))
      (node (ref "R42") (pin "1") (pinfunction "1_1") (pintype "passive"))
      (node (ref "R43") (pin "1") (pinfunction "1_1") (pintype "passive"))
      (node (ref "R45") (pin "1") (pinfunction "1_1") (pintype "passive"))
      (node (ref "R5") (pin "1") (pinfunction "1_1") (pintype "passive"))
      (node (ref "R7") (pin "1") (pinfunction "1_1") (pintype "passive"))
      (node (ref "R9") (pin "1") (pinfunction "1_1") (pintype "passive"))
      (node (ref "X2") (pin "1") (pinfunction "SK_1") (pintype "passive"))
      (node (ref "X5") (pin "4") (pinfunction "SK_4") (pintype "passive"))
      (node (ref "X7") (pin "4") (pinfunction "SK_4") (pintype "passive"))
      (node (ref "X8") (pin "2") (pinfunction "SK_2") (pintype "passive"))
    )
    (net (code "19") (name "I1") (class "Default")
      (node (ref "IC4") (pin "7") (pinfunction "VOUT_7") (pintype "output"))
      (node (ref "R34") (pin "2") (pinfunction "2_2") (pintype "passive"))
    )
    (net (code "20") (name "I2") (class "Default")
      (node (ref "IC6") (pin "7") (pinfunction "VOUT_7") (pintype "output"))
      (node (ref "R39") (pin "2") (pinfunction "2_2") (pintype "passive"))
    )
    (net (code "21") (name "Net-(IC3-AREF)") (class "Default")
      (node (ref "C20") (pin "+") (pinfunction "+_+") (pintype "passive"))
      (node (ref "IC3") (pin "20") (pinfunction "AREF_20") (pintype "passive"))
    )
    (net (code "22") (name "Net-(IC3-PB2(SS{slash}OC1B))") (class "Default")
      (node (ref "IC3") (pin "14") (pinfunction "PB2(SS/OC1B)_14") (pintype "bidirectional"))
      (node (ref "IC5") (pin "14") (pinfunction "PB2(SS/OC1B)_14") (pintype "bidirectional"))
    )
    (net (code "23") (name "Net-(IC3-PB3(MOSI{slash}OC2))") (class "Default")
      (node (ref "IC3") (pin "15") (pinfunction "PB3(MOSI/OC2)_15") (pintype "bidirectional"))
      (node (ref "JP1") (pin "5") (pinfunction "5_5") (pintype "passive"))
      (node (ref "P1") (pin "5-MOSI") (pinfunction "5_5-MOSI") (pintype "bidirectional"))
    )
    (net (code "24") (name "Net-(IC3-PB4(MISO))") (class "Default")
      (node (ref "IC3") (pin "16") (pinfunction "PB4(MISO)_16") (pintype "bidirectional"))
      (node (ref "JP1") (pin "3") (pinfunction "3_3") (pintype "passive"))
      (node (ref "P1") (pin "4-MISO") (pinfunction "4_4-MISO") (pintype "bidirectional"))
    )
    (net (code "25") (name "Net-(IC3-PB5(SCK))") (class "Default")
      (node (ref "IC3") (pin "17") (pinfunction "PB5(SCK)_17") (pintype "bidirectional"))
      (node (ref "JP1") (pin "1") (pinfunction "1_1") (pintype "passive"))
      (node (ref "P1") (pin "3-SCK") (pinfunction "3_3-SCK") (pintype "bidirectional"))
    )
    (net (code "26") (name "Net-(IC3-PB6(XTAL1{slash}TOSC1))") (class "Default")
      (node (ref "C23") (pin "1") (pinfunction "1_1") (pintype "passive"))
      (node (ref "IC3") (pin "7") (pinfunction "PB6(XTAL1/TOSC1)_7") (pintype "bidirectional"))
      (node (ref "Q1") (pin "2") (pinfunction "2_2") (pintype "passive"))
    )
    (net (code "27") (name "Net-(IC3-PB7(XTAL2{slash}TOSC2))") (class "Default")
      (node (ref "C22") (pin "1") (pinfunction "1_1") (pintype "passive"))
      (node (ref "IC3") (pin "8") (pinfunction "PB7(XTAL2/TOSC2)_8") (pintype "bidirectional"))
      (node (ref "Q1") (pin "1") (pinfunction "1_1") (pintype "passive"))
    )
    (net (code "28") (name "Net-(IC3-PC6({slash}RESET))") (class "Default")
      (node (ref "C21") (pin "+") (pinfunction "+_+") (pintype "passive"))
      (node (ref "IC3") (pin "29") (pinfunction "PC6(/RESET)_29") (pintype "bidirectional"))
      (node (ref "P1") (pin "2-RST") (pinfunction "2_2-RST") (pintype "bidirectional"))
      (node (ref "R28") (pin "1") (pinfunction "1_1") (pintype "passive"))
    )
    (net (code "29") (name "Net-(IC3-PD3(INT1))") (class "Default")
      (node (ref "IC3") (pin "1") (pinfunction "PD3(INT1)_1") (pintype "bidirectional"))
      (node (ref "X5") (pin "1") (pinfunction "SK_1") (pintype "passive"))
    )
    (net (code "30") (name "Net-(IC4-FILTER)") (class "Default")
      (node (ref "C24") (pin "1") (pinfunction "1_1") (pintype "passive"))
      (node (ref "IC4") (pin "6") (pinfunction "FILTER_6") (pintype "bidirectional"))
    )
    (net (code "31") (name "Net-(IC4-IP+)") (class "Default")
      (node (ref "IC4") (pin "1") (pinfunction "IP+_1") (pintype "passive"))
      (node (ref "IC4") (pin "2") (pinfunction "IP+1_2") (pintype "passive"))
      (node (ref "X3") (pin "1") (pinfunction "1_1") (pintype "passive"))
    )
    (net (code "32") (name "Net-(IC4-IP-)") (class "Default")
      (node (ref "IC4") (pin "3") (pinfunction "IP-_3") (pintype "passive"))
      (node (ref "IC4") (pin "4") (pinfunction "IP-1_4") (pintype "passive"))
      (node (ref "X3") (pin "2") (pinfunction "1_2") (pintype "passive"))
    )
    (net (code "33") (name "Net-(IC5-AREF)") (class "Default")
      (node (ref "C32") (pin "+") (pinfunction "+_+") (pintype "passive"))
      (node (ref "IC5") (pin "20") (pinfunction "AREF_20") (pintype "passive"))
    )
    (net (code "34") (name "Net-(IC5-PB3(MOSI{slash}OC2))") (class "Default")
      (node (ref "IC5") (pin "15") (pinfunction "PB3(MOSI/OC2)_15") (pintype "bidirectional"))
      (node (ref "JP1") (pin "6") (pinfunction "6_6") (pintype "passive"))
      (node (ref "P2") (pin "5-MOSI") (pinfunction "5_5-MOSI") (pintype "bidirectional"))
    )
    (net (code "35") (name "Net-(IC5-PB4(MISO))") (class "Default")
      (node (ref "IC5") (pin "16") (pinfunction "PB4(MISO)_16") (pintype "bidirectional"))
      (node (ref "JP1") (pin "4") (pinfunction "4_4") (pintype "passive"))
      (node (ref "P2") (pin "4-MISO") (pinfunction "4_4-MISO") (pintype "bidirectional"))
    )
    (net (code "36") (name "Net-(IC5-PB5(SCK))") (class "Default")
      (node (ref "IC5") (pin "17") (pinfunction "PB5(SCK)_17") (pintype "bidirectional"))
      (node (ref "JP1") (pin "2") (pinfunction "2_2") (pintype "passive"))
      (node (ref "P2") (pin "3-SCK") (pinfunction "3_3-SCK") (pintype "bidirectional"))
    )
    (net (code "37") (name "Net-(IC5-PC6({slash}RESET))") (class "Default")
      (node (ref "C33") (pin "+") (pinfunction "+_+") (pintype "passive"))
      (node (ref "IC5") (pin "29") (pinfunction "PC6(/RESET)_29") (pintype "bidirectional"))
      (node (ref "P2") (pin "2-RST") (pinfunction "2_2-RST") (pintype "bidirectional"))
      (node (ref "R30") (pin "1") (pinfunction "1_1") (pintype "passive"))
    )
    (net (code "38") (name "Net-(IC6-FILTER)") (class "Default")
      (node (ref "C25") (pin "1") (pinfunction "1_1") (pintype "passive"))
      (node (ref "IC6") (pin "6") (pinfunction "FILTER_6") (pintype "bidirectional"))
    )
    (net (code "39") (name "Net-(IC6-IP+)") (class "Default")
      (node (ref "IC6") (pin "1") (pinfunction "IP+_1") (pintype "passive"))
      (node (ref "IC6") (pin "2") (pinfunction "IP+1_2") (pintype "passive"))
      (node (ref "X4") (pin "1") (pinfunction "1_1") (pintype "passive"))
    )
    (net (code "40") (name "Net-(IC6-IP-)") (class "Default")
      (node (ref "IC6") (pin "3") (pinfunction "IP-_3") (pintype "passive"))
      (node (ref "IC6") (pin "4") (pinfunction "IP-1_4") (pintype "passive"))
      (node (ref "X4") (pin "2") (pinfunction "1_2") (pintype "passive"))
    )
    (net (code "41") (name "Net-(IC7A-+IN)") (class "Default")
      (node (ref "C26") (pin "1") (pinfunction "1_1") (pintype "passive"))
      (node (ref "IC7") (pin "3") (pinfunction "+IN_3") (pintype "input"))
      (node (ref "R29") (pin "1") (pinfunction "1_1") (pintype "passive"))
      (node (ref "R31") (pin "2") (pinfunction "2_2") (pintype "passive"))
    )
    (net (code "42") (name "Net-(IC7A--IN)") (class "Default")
      (node (ref "IC7") (pin "1") (pinfunction "OUT_1") (pintype "output"))
      (node (ref "IC7") (pin "2") (pinfunction "-IN_2") (pintype "input"))
      (node (ref "R32") (pin "2") (pinfunction "2_2") (pintype "passive"))
    )
    (net (code "43") (name "Net-(IC7B-+IN)") (class "Default")
      (node (ref "C27") (pin "1") (pinfunction "1_1") (pintype "passive"))
      (node (ref "IC7") (pin "5") (pinfunction "+IN_5") (pintype "input"))
      (node (ref "R34") (pin "1") (pinfunction "1_1") (pintype "passive"))
    )
    (net (code "44") (name "Net-(IC7B--IN)") (class "Default")
      (node (ref "C28") (pin "2") (pinfunction "2_2") (pintype "passive"))
      (node (ref "IC7") (pin "6") (pinfunction "-IN_6") (pintype "input"))
      (node (ref "R32") (pin "1") (pinfunction "1_1") (pintype "passive"))
      (node (ref "R33") (pin "2") (pinfunction "2_2") (pintype "passive"))
    )
    (net (code "45") (name "Net-(IC8A-+IN)") (class "Default")
      (node (ref "C29") (pin "1") (pinfunction "1_1") (pintype "passive"))
      (node (ref "IC8") (pin "3") (pinfunction "+IN_3") (pintype "input"))
      (node (ref "R35") (pin "1") (pinfunction "1_1") (pintype "passive"))
      (node (ref "R36") (pin "2") (pinfunction "2_2") (pintype "passive"))
    )
    (net (code "46") (name "Net-(IC8A--IN)") (class "Default")
      (node (ref "IC8") (pin "1") (pinfunction "OUT_1") (pintype "output"))
      (node (ref "IC8") (pin "2") (pinfunction "-IN_2") (pintype "input"))
      (node (ref "R37") (pin "2") (pinfunction "2_2") (pintype "passive"))
    )
    (net (code "47") (name "Net-(IC8B-+IN)") (class "Default")
      (node (ref "C36") (pin "1") (pinfunction "1_1") (pintype "passive"))
      (node (ref "IC8") (pin "5") (pinfunction "+IN_5") (pintype "input"))
      (node (ref "R39") (pin "1") (pinfunction "1_1") (pintype "passive"))
    )
    (net (code "48") (name "Net-(IC8B--IN)") (class "Default")
      (node (ref "C37") (pin "2") (pinfunction "2_2") (pintype "passive"))
      (node (ref "IC8") (pin "6") (pinfunction "-IN_6") (pintype "input"))
      (node (ref "R37") (pin "1") (pinfunction "1_1") (pintype "passive"))
      (node (ref "R38") (pin "2") (pinfunction "2_2") (pintype "passive"))
    )
    (net (code "49") (name "Net-(IC9-FB)") (class "Default")
      (node (ref "IC9") (pin "4") (pinfunction "FB_4") (pintype "input"))
      (node (ref "R1") (pin "2") (pinfunction "2_2") (pintype "passive"))
      (node (ref "R2") (pin "1") (pinfunction "1_1") (pintype "passive"))
    )
    (net (code "50") (name "Net-(IC9-OUT)") (class "Default")
      (node (ref "D1") (pin "C") (pinfunction "C_C") (pintype "passive"))
      (node (ref "IC9") (pin "2") (pinfunction "OUT_2") (pintype "output"))
      (node (ref "L1") (pin "1") (pinfunction "1_1") (pintype "passive"))
    )
    (net (code "51") (name "Net-(IC10-FB)") (class "Default")
      (node (ref "IC10") (pin "4") (pinfunction "FB_4") (pintype "input"))
      (node (ref "R45") (pin "2") (pinfunction "2_2") (pintype "passive"))
      (node (ref "R46") (pin "1") (pinfunction "1_1") (pintype "passive"))
    )
    (net (code "52") (name "Net-(IC10-IN)") (class "Default")
      (node (ref "C1") (pin "+") (pinfunction "+_+") (pintype "passive"))
      (node (ref "C35") (pin "+") (pinfunction "+_+") (pintype "passive"))
      (node (ref "D2") (pin "C") (pinfunction "C_C") (pintype "passive"))
      (node (ref "IC10") (pin "1") (pinfunction "IN_1") (pintype "input"))
      (node (ref "IC9") (pin "1") (pinfunction "IN_1") (pintype "input"))
    )
    (net (code "53") (name "Net-(IC10-OUT)") (class "Default")
      (node (ref "D3") (pin "C") (pinfunction "C_C") (pintype "passive"))
      (node (ref "IC10") (pin "2") (pinfunction "OUT_2") (pintype "output"))
      (node (ref "L2") (pin "1") (pinfunction "1_1") (pintype "passive"))
    )
    (net (code "54") (name "Net-(LED1-PadA)") (class "Default")
      (node (ref "LED1") (pin "A") (pinfunction "A_A") (pintype "passive"))
      (node (ref "R40") (pin "1") (pinfunction "1_1") (pintype "passive"))
    )
    (net (code "55") (name "Net-(X5C-SK)") (class "Default")
      (node (ref "R43") (pin "2") (pinfunction "2_2") (pintype "passive"))
      (node (ref "R44") (pin "2") (pinfunction "2_2") (pintype "passive"))
      (node (ref "X5") (pin "3") (pinfunction "SK_3") (pintype "passive"))
    )
    (net (code "56") (name "Net-(X6D-SK)") (class "Default")
      (node (ref "R26") (pin "2") (pinfunction "2_2") (pintype "passive"))
      (node (ref "X6") (pin "4") (pinfunction "SK_4") (pintype "passive"))
    )
    (net (code "57") (name "Net-(X7A-SK)") (class "Default")
      (node (ref "R24") (pin "2") (pinfunction "2_2") (pintype "passive"))
      (node (ref "X7") (pin "1") (pinfunction "SK_1") (pintype "passive"))
    )
    (net (code "58") (name "RS485A") (class "Default")
      (node (ref "IC2") (pin "6") (pinfunction "A_6") (pintype "bidirectional"))
      (node (ref "R3") (pin "1") (pinfunction "1_1") (pintype "passive"))
      (node (ref "R41") (pin "2") (pinfunction "2_2") (pintype "passive"))
      (node (ref "X7") (pin "2") (pinfunction "SK_2") (pintype "passive"))
    )
    (net (code "59") (name "RS485B") (class "Default")
      (node (ref "IC2") (pin "7") (pinfunction "B_7") (pintype "bidirectional"))
      (node (ref "R41") (pin "1") (pinfunction "1_1") (pintype "passive"))
      (node (ref "R42") (pin "2") (pinfunction "2_2") (pintype "passive"))
      (node (ref "X7") (pin "3") (pinfunction "SK_3") (pintype "passive"))
    )
    (net (code "60") (name "RXD") (class "Default")
      (node (ref "IC2") (pin "1") (pinfunction "RO_1") (pintype "output"))
      (node (ref "IC3") (pin "30") (pinfunction "PD0(RXD)_30") (pintype "bidirectional"))
    )
    (net (code "61") (name "SINALIZA") (class "Default")
      (node (ref "IC3") (pin "12") (pinfunction "PB0(ICP)_12") (pintype "bidirectional"))
      (node (ref "R40") (pin "2") (pinfunction "2_2") (pintype "passive"))
    )
    (net (code "62") (name "TEMP_IN") (class "Default")
      (node (ref "C34") (pin "+") (pinfunction "+_+") (pintype "passive"))
      (node (ref "IC5") (pin "27") (pinfunction "PC4(ADC4/SDA)_27") (pintype "bidirectional"))
      (node (ref "R44") (pin "1") (pinfunction "1_1") (pintype "passive"))
    )
    (net (code "63") (name "TXD") (class "Default")
      (node (ref "IC2") (pin "4") (pinfunction "DI_4") (pintype "input"))
      (node (ref "IC3") (pin "31") (pinfunction "PD1(TXD)_31") (pintype "bidirectional"))
    )
    (net (code "64") (name "TXE") (class "Default")
      (node (ref "IC2") (pin "2") (pinfunction "~{RE}_2") (pintype "input"))
      (node (ref "IC2") (pin "3") (pinfunction "DE_3") (pintype "input"))
      (node (ref "IC3") (pin "2") (pinfunction "PD4(XCK/T0)_2") (pintype "bidirectional"))
    )
    (net (code "65") (name "VC1") (class "Default")
      (node (ref "R4") (pin "2") (pinfunction "2_2") (pintype "passive"))
      (node (ref "X2") (pin "2") (pinfunction "SK_2") (pintype "passive"))
    )
    (net (code "66") (name "VC2") (class "Default")
      (node (ref "R6") (pin "2") (pinfunction "2_2") (pintype "passive"))
      (node (ref "X2") (pin "3") (pinfunction "SK_3") (pintype "passive"))
    )
    (net (code "67") (name "VC3") (class "Default")
      (node (ref "R8") (pin "2") (pinfunction "2_2") (pintype "passive"))
      (node (ref "X2") (pin "4") (pinfunction "SK_4") (pintype "passive"))
    )
    (net (code "68") (name "VC4") (class "Default")
      (node (ref "R10") (pin "2") (pinfunction "2_2") (pintype "passive"))
      (node (ref "X1") (pin "1") (pinfunction "SK_1") (pintype "passive"))
    )
    (net (code "69") (name "VC5") (class "Default")
      (node (ref "R12") (pin "2") (pinfunction "2_2") (pintype "passive"))
      (node (ref "X1") (pin "2") (pinfunction "SK_2") (pintype "passive"))
    )
    (net (code "70") (name "VC6") (class "Default")
      (node (ref "R14") (pin "2") (pinfunction "2_2") (pintype "passive"))
      (node (ref "X1") (pin "3") (pinfunction "SK_3") (pintype "passive"))
    )
    (net (code "71") (name "VC7") (class "Default")
      (node (ref "R16") (pin "2") (pinfunction "2_2") (pintype "passive"))
      (node (ref "X1") (pin "4") (pinfunction "SK_4") (pintype "passive"))
    )
    (net (code "72") (name "VC8") (class "Default")
      (node (ref "R18") (pin "2") (pinfunction "2_2") (pintype "passive"))
      (node (ref "X6") (pin "1") (pinfunction "SK_1") (pintype "passive"))
    )
    (net (code "73") (name "VC9") (class "Default")
      (node (ref "R20") (pin "2") (pinfunction "2_2") (pintype "passive"))
      (node (ref "X6") (pin "2") (pinfunction "SK_2") (pintype "passive"))
    )
    (net (code "74") (name "VC10") (class "Default")
      (node (ref "R22") (pin "2") (pinfunction "2_2") (pintype "passive"))
      (node (ref "X6") (pin "3") (pinfunction "SK_3") (pintype "passive"))
    )
    (net (code "75") (name "VIN") (class "Default")
      (node (ref "D2") (pin "A") (pinfunction "A_A") (pintype "passive"))
      (node (ref "X8") (pin "1") (pinfunction "SK_1") (pintype "passive"))
    )
    (net (code "76") (name "unconnected-(IC3-PB1(OC1A)-Pad13)") (class "Default")
      (node (ref "IC3") (pin "13") (pinfunction "PB1(OC1A)_13") (pintype "bidirectional"))
    )
    (net (code "77") (name "unconnected-(IC3-PD2(INT0)-Pad32)") (class "Default")
      (node (ref "IC3") (pin "32") (pinfunction "PD2(INT0)_32") (pintype "bidirectional"))
    )
    (net (code "78") (name "unconnected-(IC3-PD5(T1)-Pad9)") (class "Default")
      (node (ref "IC3") (pin "9") (pinfunction "PD5(T1)_9") (pintype "bidirectional"))
    )
    (net (code "79") (name "unconnected-(IC3-PD6(AIN0)-Pad10)") (class "Default")
      (node (ref "IC3") (pin "10") (pinfunction "PD6(AIN0)_10") (pintype "bidirectional"))
    )
    (net (code "80") (name "unconnected-(IC3-PD7(AIN1)-Pad11)") (class "Default")
      (node (ref "IC3") (pin "11") (pinfunction "PD7(AIN1)_11") (pintype "bidirectional"))
    )
    (net (code "81") (name "unconnected-(IC5-PB0(ICP)-Pad12)") (class "Default")
      (node (ref "IC5") (pin "12") (pinfunction "PB0(ICP)_12") (pintype "bidirectional"))
    )
    (net (code "82") (name "unconnected-(IC5-PB1(OC1A)-Pad13)") (class "Default")
      (node (ref "IC5") (pin "13") (pinfunction "PB1(OC1A)_13") (pintype "bidirectional"))
    )
    (net (code "83") (name "unconnected-(IC5-PB6(XTAL1{slash}TOSC1)-Pad7)") (class "Default")
      (node (ref "IC5") (pin "7") (pinfunction "PB6(XTAL1/TOSC1)_7") (pintype "bidirectional"))
    )
    (net (code "84") (name "unconnected-(IC5-PB7(XTAL2{slash}TOSC2)-Pad8)") (class "Default")
      (node (ref "IC5") (pin "8") (pinfunction "PB7(XTAL2/TOSC2)_8") (pintype "bidirectional"))
    )
    (net (code "85") (name "unconnected-(IC5-PC5(ADC5{slash}SCL)-Pad28)") (class "Default")
      (node (ref "IC5") (pin "28") (pinfunction "PC5(ADC5/SCL)_28") (pintype "bidirectional"))
    )
    (net (code "86") (name "unconnected-(IC5-PD0(RXD)-Pad30)") (class "Default")
      (node (ref "IC5") (pin "30") (pinfunction "PD0(RXD)_30") (pintype "bidirectional"))
    )
    (net (code "87") (name "unconnected-(IC5-PD1(TXD)-Pad31)") (class "Default")
      (node (ref "IC5") (pin "31") (pinfunction "PD1(TXD)_31") (pintype "bidirectional"))
    )
    (net (code "88") (name "unconnected-(IC5-PD2(INT0)-Pad32)") (class "Default")
      (node (ref "IC5") (pin "32") (pinfunction "PD2(INT0)_32") (pintype "bidirectional"))
    )
    (net (code "89") (name "unconnected-(IC5-PD3(INT1)-Pad1)") (class "Default")
      (node (ref "IC5") (pin "1") (pinfunction "PD3(INT1)_1") (pintype "bidirectional"))
    )
    (net (code "90") (name "unconnected-(IC5-PD4(XCK{slash}T0)-Pad2)") (class "Default")
      (node (ref "IC5") (pin "2") (pinfunction "PD4(XCK/T0)_2") (pintype "bidirectional"))
    )
    (net (code "91") (name "unconnected-(IC5-PD5(T1)-Pad9)") (class "Default")
      (node (ref "IC5") (pin "9") (pinfunction "PD5(T1)_9") (pintype "bidirectional"))
    )
    (net (code "92") (name "unconnected-(IC5-PD6(AIN0)-Pad10)") (class "Default")
      (node (ref "IC5") (pin "10") (pinfunction "PD6(AIN0)_10") (pintype "bidirectional"))
    )
    (net (code "93") (name "unconnected-(IC5-PD7(AIN1)-Pad11)") (class "Default")
      (node (ref "IC5") (pin "11") (pinfunction "PD7(AIN1)_11") (pintype "bidirectional"))
    )
  )
)
